# driver.net
KiCad netlist of a schematic drawn in EAGLE
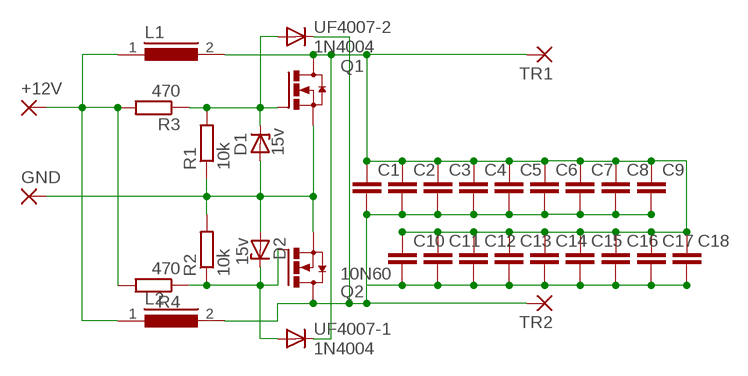
[diagram p0: schematic, sheet 1]

(export (version "E")
  (design (tool "Eeschema 10.0.6"))
  (components
    (comp (ref "+12V")
      (value "3,17/1,1")
      (footprint "eagle-import:3,17_1,1")
      (libsource (lib "eagle-import") (part "3,17/1,1"))
    )
    (comp (ref "C1")
      (value "C-EU150-064X183")
      (footprint "eagle-import:C150-064X183")
      (libsource (lib "eagle-import") (part "C-EU150-064X183"))
    )
    (comp (ref "C2")
      (value "C-EU150-064X183")
      (footprint "eagle-import:C150-064X183")
      (libsource (lib "eagle-import") (part "C-EU150-064X183"))
    )
    (comp (ref "C3")
      (value "C-EU150-064X183")
      (footprint "eagle-import:C150-064X183")
      (libsource (lib "eagle-import") (part "C-EU150-064X183"))
    )
    (comp (ref "C4")
      (value "C-EU150-064X183")
      (footprint "eagle-import:C150-064X183")
      (libsource (lib "eagle-import") (part "C-EU150-064X183"))
    )
    (comp (ref "C5")
      (value "C-EU150-064X183")
      (footprint "eagle-import:C150-064X183")
      (libsource (lib "eagle-import") (part "C-EU150-064X183"))
    )
    (comp (ref "C6")
      (value "C-EU150-064X183")
      (footprint "eagle-import:C150-064X183")
      (libsource (lib "eagle-import") (part "C-EU150-064X183"))
    )
    (comp (ref "C7")
      (value "C-EU150-064X183")
      (footprint "eagle-import:C150-064X183")
      (libsource (lib "eagle-import") (part "C-EU150-064X183"))
    )
    (comp (ref "C8")
      (value "C-EU150-064X183")
      (footprint "eagle-import:C150-064X183")
      (libsource (lib "eagle-import") (part "C-EU150-064X183"))
    )
    (comp (ref "C9")
      (value "C-EU150-064X183")
      (footprint "eagle-import:C150-064X183")
      (libsource (lib "eagle-import") (part "C-EU150-064X183"))
    )
    (comp (ref "C10")
      (value "C-EU150-064X183")
      (footprint "eagle-import:C150-064X183")
      (libsource (lib "eagle-import") (part "C-EU150-064X183"))
    )
    (comp (ref "C11")
      (value "C-EU150-064X183")
      (footprint "eagle-import:C150-064X183")
      (libsource (lib "eagle-import") (part "C-EU150-064X183"))
    )
    (comp (ref "C12")
      (value "C-EU150-064X183")
      (footprint "eagle-import:C150-064X183")
      (libsource (lib "eagle-import") (part "C-EU150-064X183"))
    )
    (comp (ref "C13")
      (value "C-EU150-064X183")
      (footprint "eagle-import:C150-064X183")
      (libsource (lib "eagle-import") (part "C-EU150-064X183"))
    )
    (comp (ref "C14")
      (value "C-EU150-064X183")
      (footprint "eagle-import:C150-064X183")
      (libsource (lib "eagle-import") (part "C-EU150-064X183"))
    )
    (comp (ref "C15")
      (value "C-EU150-064X183")
      (footprint "eagle-import:C150-064X183")
      (libsource (lib "eagle-import") (part "C-EU150-064X183"))
    )
    (comp (ref "C16")
      (value "C-EU150-064X183")
      (footprint "eagle-import:C150-064X183")
      (libsource (lib "eagle-import") (part "C-EU150-064X183"))
    )
    (comp (ref "C17")
      (value "C-EU150-064X183")
      (footprint "eagle-import:C150-064X183")
      (libsource (lib "eagle-import") (part "C-EU150-064X183"))
    )
    (comp (ref "C18")
      (value "C-EU150-064X183")
      (footprint "eagle-import:C150-064X183")
      (libsource (lib "eagle-import") (part "C-EU150-064X183"))
    )
    (comp (ref "D1")
      (value "15v")
      (footprint "eagle-import:DO35Z10")
      (libsource (lib "eagle-import") (part "ZENER-DIODEDO35Z10"))
    )
    (comp (ref "D2")
      (value "15v")
      (footprint "eagle-import:DO35Z10")
      (libsource (lib "eagle-import") (part "ZENER-DIODEDO35Z10"))
    )
    (comp (ref "GND")
      (value "3,17/1,1")
      (footprint "eagle-import:3,17_1,1")
      (libsource (lib "eagle-import") (part "3,17/1,1"))
    )
    (comp (ref "L1")
      (value "R2408F11")
      (footprint "eagle-import:11-24")
      (libsource (lib "eagle-import") (part "R2408F11"))
    )
    (comp (ref "L2")
      (value "R2408F11")
      (footprint "eagle-import:11-24")
      (libsource (lib "eagle-import") (part "R2408F11"))
    )
    (comp (ref "Q1")
      (value "IRFP250")
      (footprint "eagle-import:TO-247AD-V")
      (libsource (lib "eagle-import") (part "IRFP250"))
    )
    (comp (ref "Q2")
      (value "10N60")
      (footprint "eagle-import:TO-247AD-V")
      (libsource (lib "eagle-import") (part "IRFP250"))
    )
    (comp (ref "R1")
      (value "10k")
      (footprint "eagle-import:0204_7")
      (libsource (lib "eagle-import") (part "R-EU_0204/7"))
    )
    (comp (ref "R2")
      (value "10k")
      (footprint "eagle-import:0204_7")
      (libsource (lib "eagle-import") (part "R-EU_0204/7"))
    )
    (comp (ref "R3")
      (value "470")
      (footprint "eagle-import:0617_17")
      (libsource (lib "eagle-import") (part "R-EU_0617/17"))
    )
    (comp (ref "R4")
      (value "470")
      (footprint "eagle-import:0617_17")
      (libsource (lib "eagle-import") (part "R-EU_0617/17"))
    )
    (comp (ref "TR1")
      (value "3,17/1,1")
      (footprint "eagle-import:3,17_1,1")
      (libsource (lib "eagle-import") (part "3,17/1,1"))
    )
    (comp (ref "TR2")
      (value "3,17/1,1")
      (footprint "eagle-import:3,17_1,1")
      (libsource (lib "eagle-import") (part "3,17/1,1"))
    )
    (comp (ref "UF4007-1")
      (value "1N4004")
      (footprint "eagle-import:DO41-10")
      (libsource (lib "eagle-import") (part "1N4004"))
    )
    (comp (ref "UF4007-2")
      (value "1N4004")
      (footprint "eagle-import:DO41-10")
      (libsource (lib "eagle-import") (part "1N4004"))
    )
  )
  (nets
    (net (code "1") (name "Net-(+12V-P)") (class "Default")
      (node (ref "+12V") (pin "1") (pinfunction "P_1") (pintype "passive"))
      (node (ref "L1") (pin "1") (pinfunction "1_1") (pintype "passive"))
      (node (ref "L2") (pin "1") (pinfunction "1_1") (pintype "passive"))
      (node (ref "R3") (pin "2") (pinfunction "2_2") (pintype "passive"))
      (node (ref "R4") (pin "2") (pinfunction "2_2") (pintype "passive"))
    )
    (net (code "2") (name "Net-(D1-PadC)") (class "Default")
      (node (ref "D1") (pin "C") (pinfunction "C_C") (pintype "passive"))
      (node (ref "Q1") (pin "G") (pinfunction "G_G") (pintype "passive"))
      (node (ref "R1") (pin "2") (pinfunction "2_2") (pintype "passive"))
      (node (ref "R3") (pin "1") (pinfunction "1_1") (pintype "passive"))
      (node (ref "UF4007-2") (pin "A") (pinfunction "A_A") (pintype "passive"))
    )
    (net (code "3") (name "Net-(D2-PadC)") (class "Default")
      (node (ref "D2") (pin "C") (pinfunction "C_C") (pintype "passive"))
      (node (ref "Q2") (pin "G") (pinfunction "G_G") (pintype "passive"))
      (node (ref "R2") (pin "1") (pinfunction "1_1") (pintype "passive"))
      (node (ref "R4") (pin "1") (pinfunction "1_1") (pintype "passive"))
      (node (ref "UF4007-1") (pin "A") (pinfunction "A_A") (pintype "passive"))
    )
    (net (code "4") (name "Net-(GND-P)") (class "Default")
      (node (ref "D1") (pin "A") (pinfunction "A_A") (pintype "passive"))
      (node (ref "D2") (pin "A") (pinfunction "A_A") (pintype "passive"))
      (node (ref "GND") (pin "1") (pinfunction "P_1") (pintype "passive"))
      (node (ref "Q1") (pin "S") (pinfunction "S_S") (pintype "passive"))
      (node (ref "Q2") (pin "S") (pinfunction "S_S") (pintype "passive"))
      (node (ref "R1") (pin "1") (pinfunction "1_1") (pintype "passive"))
      (node (ref "R2") (pin "2") (pinfunction "2_2") (pintype "passive"))
    )
    (net (code "5") (name "Net-(TR1-P)") (class "Default")
      (node (ref "C1") (pin "1") (pinfunction "1_1") (pintype "passive"))
      (node (ref "C10") (pin "1") (pinfunction "1_1") (pintype "passive"))
      (node (ref "C11") (pin "1") (pinfunction "1_1") (pintype "passive"))
      (node (ref "C12") (pin "1") (pinfunction "1_1") (pintype "passive"))
      (node (ref "C13") (pin "1") (pinfunction "1_1") (pintype "passive"))
      (node (ref "C14") (pin "1") (pinfunction "1_1") (pintype "passive"))
      (node (ref "C15") (pin "1") (pinfunction "1_1") (pintype "passive"))
      (node (ref "C16") (pin "1") (pinfunction "1_1") (pintype "passive"))
      (node (ref "C17") (pin "1") (pinfunction "1_1") (pintype "passive"))
      (node (ref "C18") (pin "1") (pinfunction "1_1") (pintype "passive"))
      (node (ref "C2") (pin "1") (pinfunction "1_1") (pintype "passive"))
      (node (ref "C3") (pin "1") (pinfunction "1_1") (pintype "passive"))
      (node (ref "C4") (pin "1") (pinfunction "1_1") (pintype "passive"))
      (node (ref "C5") (pin "1") (pinfunction "1_1") (pintype "passive"))
      (node (ref "C6") (pin "1") (pinfunction "1_1") (pintype "passive"))
      (node (ref "C7") (pin "1") (pinfunction "1_1") (pintype "passive"))
      (node (ref "C8") (pin "1") (pinfunction "1_1") (pintype "passive"))
      (node (ref "C9") (pin "1") (pinfunction "1_1") (pintype "passive"))
      (node (ref "L1") (pin "2") (pinfunction "2_2") (pintype "passive"))
      (node (ref "Q1") (pin "D") (pinfunction "D_D") (pintype "passive"))
      (node (ref "TR1") (pin "1") (pinfunction "P_1") (pintype "passive"))
      (node (ref "UF4007-1") (pin "C") (pinfunction "C_C") (pintype "passive"))
    )
    (net (code "6") (name "Net-(TR2-P)") (class "Default")
      (node (ref "C1") (pin "2") (pinfunction "2_2") (pintype "passive"))
      (node (ref "C10") (pin "2") (pinfunction "2_2") (pintype "passive"))
      (node (ref "C11") (pin "2") (pinfunction "2_2") (pintype "passive"))
      (node (ref "C12") (pin "2") (pinfunction "2_2") (pintype "passive"))
      (node (ref "C13") (pin "2") (pinfunction "2_2") (pintype "passive"))
      (node (ref "C14") (pin "2") (pinfunction "2_2") (pintype "passive"))
      (node (ref "C15") (pin "2") (pinfunction "2_2") (pintype "passive"))
      (node (ref "C16") (pin "2") (pinfunction "2_2") (pintype "passive"))
      (node (ref "C17") (pin "2") (pinfunction "2_2") (pintype "passive"))
      (node (ref "C18") (pin "2") (pinfunction "2_2") (pintype "passive"))
      (node (ref "C2") (pin "2") (pinfunction "2_2") (pintype "passive"))
      (node (ref "C3") (pin "2") (pinfunction "2_2") (pintype "passive"))
      (node (ref "C4") (pin "2") (pinfunction "2_2") (pintype "passive"))
      (node (ref "C5") (pin "2") (pinfunction "2_2") (pintype "passive"))
      (node (ref "C6") (pin "2") (pinfunction "2_2") (pintype "passive"))
      (node (ref "C7") (pin "2") (pinfunction "2_2") (pintype "passive"))
      (node (ref "C8") (pin "2") (pinfunction "2_2") (pintype "passive"))
      (node (ref "C9") (pin "2") (pinfunction "2_2") (pintype "passive"))
      (node (ref "L2") (pin "2") (pinfunction "2_2") (pintype "passive"))
      (node (ref "Q2") (pin "D") (pinfunction "D_D") (pintype "passive"))
      (node (ref "TR2") (pin "1") (pinfunction "P_1") (pintype "passive"))
      (node (ref "UF4007-2") (pin "C") (pinfunction "C_C") (pintype "passive"))
    )
  )
)
